# untitled.net
KiCad netlist of a schematic drawn in EAGLE
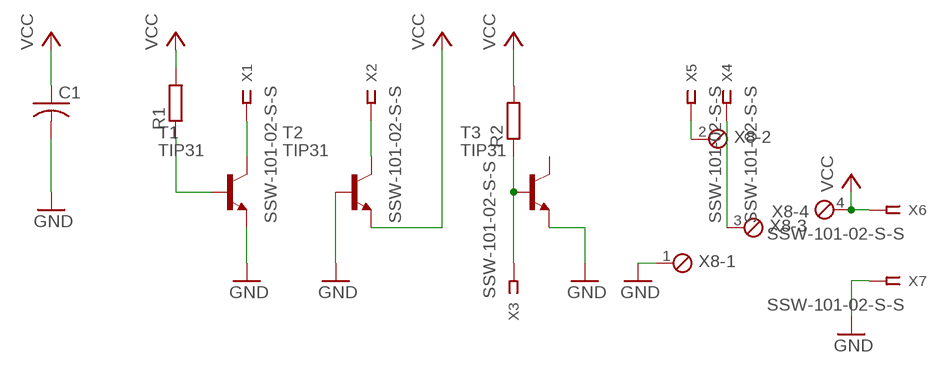
[diagram p0: schematic, sheet 1]

(export (version "E")
  (design (tool "Eeschema 10.0.6"))
  (components
    (comp (ref "C1")
      (value "C-US050-025X075")
      (footprint "eagle-import:C050-025X075")
      (libsource (lib "eagle-import") (part "C-US050-025X075"))
    )
    (comp (ref "R1")
      (value "R-EU_0204/7")
      (footprint "eagle-import:0204_7")
      (libsource (lib "eagle-import") (part "R-EU_0204/7"))
    )
    (comp (ref "R2")
      (value "R-EU_0204/7")
      (footprint "eagle-import:0204_7")
      (libsource (lib "eagle-import") (part "R-EU_0204/7"))
    )
    (comp (ref "T1")
      (value "TIP31")
      (footprint "eagle-import:TO220")
      (libsource (lib "eagle-import") (part "TIP31"))
    )
    (comp (ref "T2")
      (value "TIP31")
      (footprint "eagle-import:TO220")
      (libsource (lib "eagle-import") (part "TIP31"))
    )
    (comp (ref "T3")
      (value "TIP31")
      (footprint "eagle-import:TO220")
      (libsource (lib "eagle-import") (part "TIP31"))
    )
    (comp (ref "X1")
      (value "SSW-101-02-S-S")
      (footprint "eagle-import:SSW-101-02-S-S")
      (libsource (lib "eagle-import") (part "SSW-101-02-S-S"))
    )
    (comp (ref "X2")
      (value "SSW-101-02-S-S")
      (footprint "eagle-import:SSW-101-02-S-S")
      (libsource (lib "eagle-import") (part "SSW-101-02-S-S"))
    )
    (comp (ref "X3")
      (value "SSW-101-02-S-S")
      (footprint "eagle-import:SSW-101-02-S-S")
      (libsource (lib "eagle-import") (part "SSW-101-02-S-S"))
    )
    (comp (ref "X4")
      (value "SSW-101-02-S-S")
      (footprint "eagle-import:SSW-101-02-S-S")
      (libsource (lib "eagle-import") (part "SSW-101-02-S-S"))
    )
    (comp (ref "X5")
      (value "SSW-101-02-S-S")
      (footprint "eagle-import:SSW-101-02-S-S")
      (libsource (lib "eagle-import") (part "SSW-101-02-S-S"))
    )
    (comp (ref "X6")
      (value "SSW-101-02-S-S")
      (footprint "eagle-import:SSW-101-02-S-S")
      (libsource (lib "eagle-import") (part "SSW-101-02-S-S"))
    )
    (comp (ref "X7")
      (value "SSW-101-02-S-S")
      (footprint "eagle-import:SSW-101-02-S-S")
      (libsource (lib "eagle-import") (part "SSW-101-02-S-S"))
    )
    (comp (ref "X8")
      (value "MPT4")
      (footprint "eagle-import:4POL254")
      (libsource (lib "eagle-import") (part "MPT4"))
    )
  )
  (nets
    (net (code "1") (name "GND") (class "Default")
      (node (ref "C1") (pin "2") (pinfunction "2_2") (pintype "passive"))
      (node (ref "T1") (pin "3") (pinfunction "E_3") (pintype "passive"))
      (node (ref "T2") (pin "1") (pinfunction "B_1") (pintype "passive"))
      (node (ref "T3") (pin "3") (pinfunction "E_3") (pintype "passive"))
      (node (ref "X7") (pin "1") (pinfunction "1_1") (pintype "passive"))
      (node (ref "X8") (pin "1") (pinfunction "1_1") (pintype "passive"))
    )
    (net (code "2") (name "Net-(T1-B)") (class "Default")
      (node (ref "R1") (pin "1") (pinfunction "1_1") (pintype "passive"))
      (node (ref "T1") (pin "1") (pinfunction "B_1") (pintype "passive"))
    )
    (net (code "3") (name "Net-(T1-C)") (class "Default")
      (node (ref "T1") (pin "2") (pinfunction "C_2") (pintype "passive"))
      (node (ref "X1") (pin "1") (pinfunction "1_1") (pintype "passive"))
    )
    (net (code "4") (name "Net-(T2-C)") (class "Default")
      (node (ref "T2") (pin "2") (pinfunction "C_2") (pintype "passive"))
      (node (ref "X2") (pin "1") (pinfunction "1_1") (pintype "passive"))
    )
    (net (code "5") (name "Net-(T3-B)") (class "Default")
      (node (ref "R2") (pin "1") (pinfunction "1_1") (pintype "passive"))
      (node (ref "T3") (pin "1") (pinfunction "B_1") (pintype "passive"))
      (node (ref "X3") (pin "1") (pinfunction "1_1") (pintype "passive"))
    )
    (net (code "6") (name "Net-(X8B-1)") (class "Default")
      (node (ref "X5") (pin "1") (pinfunction "1_1") (pintype "passive"))
      (node (ref "X8") (pin "2") (pinfunction "1_2") (pintype "passive"))
    )
    (net (code "7") (name "Net-(X8C-1)") (class "Default")
      (node (ref "X4") (pin "1") (pinfunction "1_1") (pintype "passive"))
      (node (ref "X8") (pin "3") (pinfunction "1_3") (pintype "passive"))
    )
    (net (code "8") (name "VCC") (class "Default")
      (node (ref "C1") (pin "1") (pinfunction "1_1") (pintype "passive"))
      (node (ref "R1") (pin "2") (pinfunction "2_2") (pintype "passive"))
      (node (ref "R2") (pin "2") (pinfunction "2_2") (pintype "passive"))
      (node (ref "T2") (pin "3") (pinfunction "E_3") (pintype "passive"))
      (node (ref "X6") (pin "1") (pinfunction "1_1") (pintype "passive"))
      (node (ref "X8") (pin "4") (pinfunction "1_4") (pintype "passive"))
    )
    (net (code "9") (name "unconnected-(T3-C-Pad2)") (class "Default")
      (node (ref "T3") (pin "2") (pinfunction "C_2") (pintype "passive"))
    )
  )
)
